# MotorCtrl.net
KiCad netlist of a schematic drawn in Altium Designer
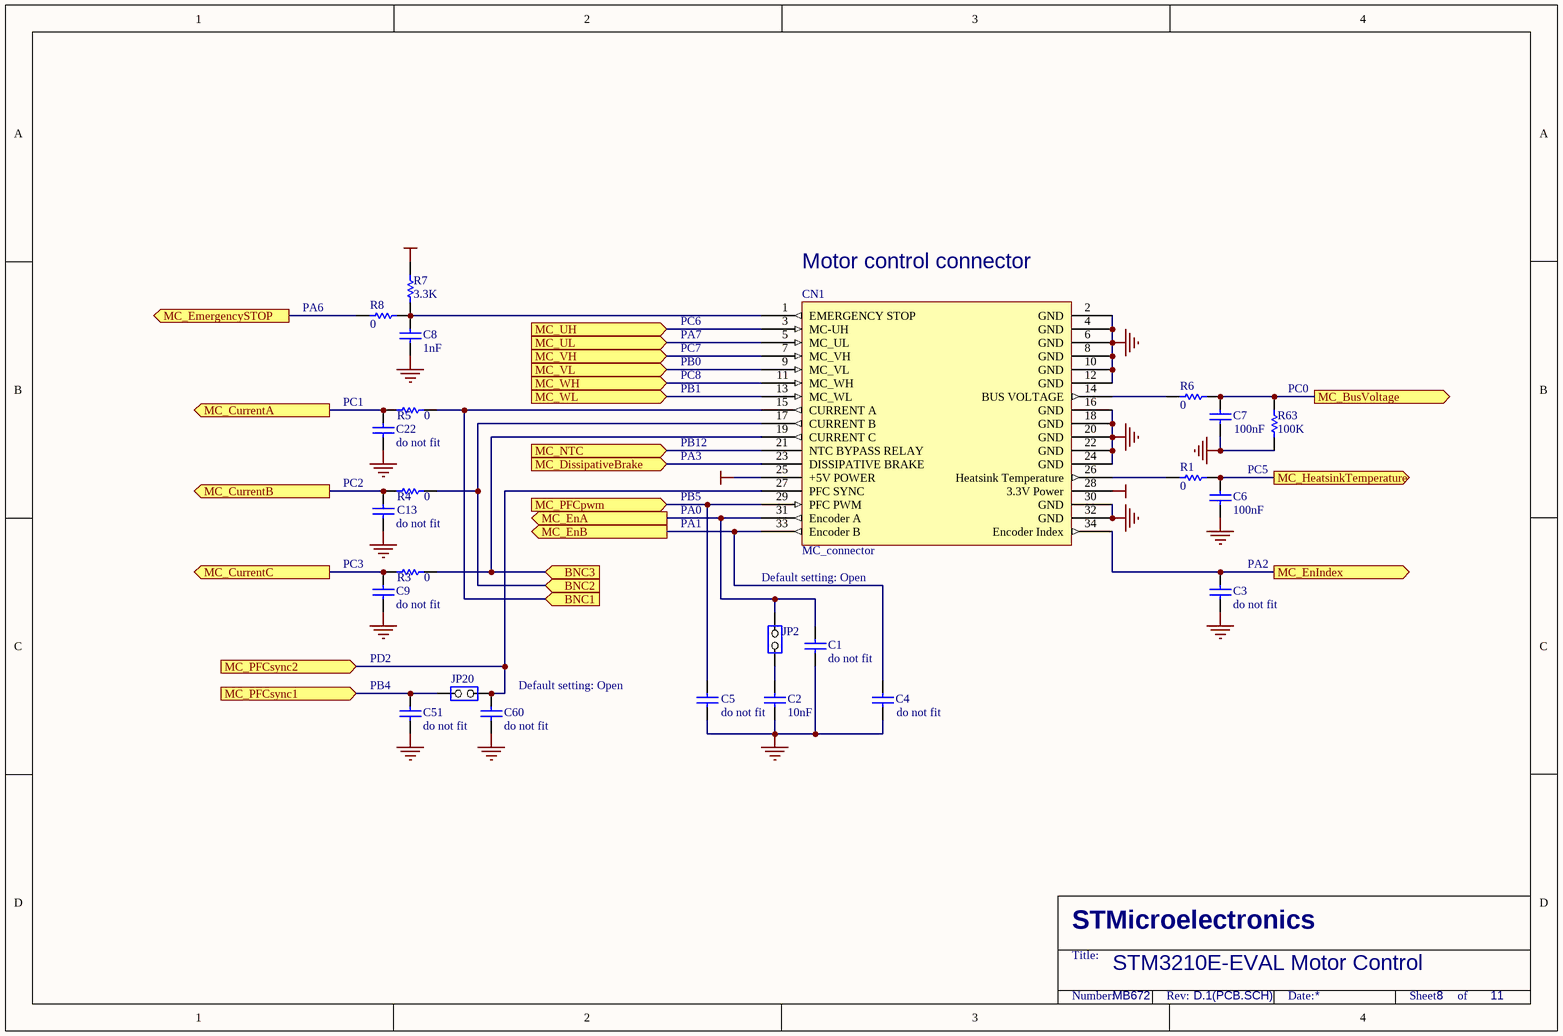
[diagram p0: MotorCtrl.SchDoc]

(export (version "E")
  (design (tool "Eeschema 10.0.6"))
  (components
    (comp (ref "C1")
      (value "do not fit")
      (description "Capacitor")
      (fields (field (name "PUBLISHER") "Altium Limited"))
      (libsource (lib "Miscellaneous Devices") (part "cap"))
    )
    (comp (ref "C2")
      (value "10nF")
      (description "Capacitor")
      (fields (field (name "PUBLISHER") "Altium Limited"))
      (libsource (lib "Miscellaneous Devices") (part "cap"))
    )
    (comp (ref "C3")
      (value "do not fit")
      (description "Capacitor")
      (fields (field (name "PUBLISHER") "Altium Limited"))
      (libsource (lib "Miscellaneous Devices") (part "cap"))
    )
    (comp (ref "C4")
      (value "do not fit")
      (description "Capacitor")
      (fields (field (name "PUBLISHER") "Altium Limited"))
      (libsource (lib "Miscellaneous Devices") (part "cap"))
    )
    (comp (ref "C5")
      (value "do not fit")
      (description "Capacitor")
      (fields (field (name "PUBLISHER") "Altium Limited"))
      (libsource (lib "Miscellaneous Devices") (part "cap"))
    )
    (comp (ref "C6")
      (value "100nF")
      (description "Capacitor")
      (fields (field (name "PUBLISHER") "Altium Limited"))
      (libsource (lib "Miscellaneous Devices") (part "cap"))
    )
    (comp (ref "C7")
      (value "100nF")
      (description "Capacitor")
      (fields (field (name "PUBLISHER") "Altium Limited"))
      (libsource (lib "Miscellaneous Devices") (part "cap"))
    )
    (comp (ref "C8")
      (value "1nF")
      (description "Capacitor")
      (fields (field (name "PUBLISHER") "Altium Limited"))
      (libsource (lib "Miscellaneous Devices") (part "CAP"))
    )
    (comp (ref "C9")
      (value "do not fit")
      (description "Capacitor")
      (fields (field (name "PUBLISHER") "Altium Limited"))
      (libsource (lib "Miscellaneous Devices") (part "cap"))
    )
    (comp (ref "C13")
      (value "do not fit")
      (description "Capacitor")
      (fields (field (name "PUBLISHER") "Altium Limited"))
      (libsource (lib "Miscellaneous Devices") (part "cap"))
    )
    (comp (ref "C22")
      (value "do not fit")
      (description "Capacitor")
      (fields (field (name "PUBLISHER") "Altium Limited"))
      (libsource (lib "Miscellaneous Devices") (part "cap"))
    )
    (comp (ref "C51")
      (value "do not fit")
      (description "Capacitor")
      (fields (field (name "PUBLISHER") "Altium Limited"))
      (libsource (lib "Miscellaneous Devices") (part "cap"))
    )
    (comp (ref "C60")
      (value "do not fit")
      (description "Capacitor")
      (fields (field (name "PUBLISHER") "Altium Limited"))
      (libsource (lib "Miscellaneous Devices") (part "cap"))
    )
    (comp (ref "CN1")
      (value "MC_connector")
      (footprint "IDC34S")
      (libsource (lib "MB525") (part "MC_connector"))
    )
    (comp (ref "JP2") (value "~") (footprint "SIP2") (libsource (lib "*") (part "JP2")))
    (comp (ref "JP20") (value "~") (footprint "SIP2") (libsource (lib "*") (part "JP2")))
    (comp (ref "R1")
      (value "0")
      (footprint "0603")
      (description "Resistor")
      (fields (field (name "PUBLISHER") "Altium Limited"))
      (libsource (lib "Miscellaneous Devices") (part "Res1"))
    )
    (comp (ref "R3")
      (value "0")
      (footprint "0603")
      (description "Resistor")
      (fields (field (name "PUBLISHER") "Altium Limited"))
      (libsource (lib "Miscellaneous Devices") (part "Res1"))
    )
    (comp (ref "R4")
      (value "0")
      (footprint "0603")
      (description "Resistor")
      (fields (field (name "PUBLISHER") "Altium Limited"))
      (libsource (lib "Miscellaneous Devices") (part "Res1"))
    )
    (comp (ref "R5")
      (value "0")
      (footprint "0603")
      (description "Resistor")
      (fields (field (name "PUBLISHER") "Altium Limited"))
      (libsource (lib "Miscellaneous Devices") (part "Res1"))
    )
    (comp (ref "R6")
      (value "0")
      (footprint "0603")
      (description "Resistor")
      (fields (field (name "PUBLISHER") "Altium Limited"))
      (libsource (lib "Miscellaneous Devices") (part "Res1"))
    )
    (comp (ref "R7")
      (value "3.3K")
      (description "Resistor")
      (fields (field (name "PUBLISHER") "Altium Limited"))
      (libsource (lib "Miscellaneous Devices") (part "Res1"))
    )
    (comp (ref "R8")
      (value "0")
      (description "Resistor")
      (fields (field (name "PUBLISHER") "Altium Limited"))
      (libsource (lib "Miscellaneous Devices") (part "Res1"))
    )
    (comp (ref "R63")
      (value "100K")
      (footprint "0603")
      (description "Resistor")
      (fields (field (name "PUBLISHER") "Altium Limited"))
      (libsource (lib "Miscellaneous Devices") (part "Res1"))
    )
  )
  (nets
    (net (code "1") (name "+3V3") (class "Default")
      (node (ref "CN1") (pin "28") (pinfunction "3.3V_Power_28") (pintype "power_in"))
      (node (ref "R7") (pin "2") (pinfunction "2_2") (pintype "passive"))
    )
    (net (code "2") (name "+5V") (class "Default")
      (node (ref "CN1") (pin "25") (pinfunction "+5V_POWER_25") (pintype "power_in"))
    )
    (net (code "3") (name "/BNC1") (class "Default")
      (node (ref "CN1") (pin "15") (pinfunction "CURRENT_A_15") (pintype "output"))
      (node (ref "R5") (pin "2") (pinfunction "2_2") (pintype "passive"))
    )
    (net (code "4") (name "/BNC2") (class "Default")
      (node (ref "CN1") (pin "17") (pinfunction "CURRENT_B_17") (pintype "output"))
      (node (ref "R4") (pin "2") (pinfunction "2_2") (pintype "passive"))
    )
    (net (code "5") (name "/BNC3") (class "Default")
      (node (ref "CN1") (pin "19") (pinfunction "CURRENT_C_19") (pintype "output"))
      (node (ref "R3") (pin "2") (pinfunction "2_2") (pintype "passive"))
    )
    (net (code "6") (name "/MC_BusVoltage") (class "Default")
      (node (ref "C7") (pin "2") (pinfunction "2_2") (pintype "passive"))
      (node (ref "R6") (pin "2") (pinfunction "2_2") (pintype "passive"))
      (node (ref "R63") (pin "2") (pinfunction "2_2") (pintype "passive"))
    )
    (net (code "7") (name "/MC_CurrentA") (class "Default")
      (node (ref "C22") (pin "2") (pinfunction "2_2") (pintype "passive"))
      (node (ref "R5") (pin "1") (pinfunction "1_1") (pintype "passive"))
    )
    (net (code "8") (name "/MC_CurrentB") (class "Default")
      (node (ref "C13") (pin "2") (pinfunction "2_2") (pintype "passive"))
      (node (ref "R4") (pin "1") (pinfunction "1_1") (pintype "passive"))
    )
    (net (code "9") (name "/MC_CurrentC") (class "Default")
      (node (ref "C9") (pin "2") (pinfunction "2_2") (pintype "passive"))
      (node (ref "R3") (pin "1") (pinfunction "1_1") (pintype "passive"))
    )
    (net (code "10") (name "/MC_DissipativeBrake") (class "Default")
      (node (ref "CN1") (pin "23") (pinfunction "DISSIPATIVE_BRAKE_23") (pintype "passive"))
    )
    (net (code "11") (name "/MC_EmergencySTOP") (class "Default")
      (node (ref "R8") (pin "2") (pinfunction "2_2") (pintype "passive"))
    )
    (net (code "12") (name "/MC_EnA") (class "Default")
      (node (ref "C1") (pin "2") (pinfunction "2_2") (pintype "passive"))
      (node (ref "CN1") (pin "31") (pinfunction "Encoder_A_31") (pintype "output"))
      (node (ref "JP2") (pin "1") (pinfunction "COMMON_1") (pintype "passive"))
    )
    (net (code "13") (name "/MC_EnB") (class "Default")
      (node (ref "C4") (pin "2") (pinfunction "2_2") (pintype "passive"))
      (node (ref "CN1") (pin "33") (pinfunction "Encoder_B_33") (pintype "output"))
    )
    (net (code "14") (name "/MC_EnIndex") (class "Default")
      (node (ref "C3") (pin "2") (pinfunction "2_2") (pintype "passive"))
      (node (ref "CN1") (pin "34") (pinfunction "Encoder_Index_34") (pintype "output"))
    )
    (net (code "15") (name "/MC_HeatsinkTemperature") (class "Default")
      (node (ref "C6") (pin "2") (pinfunction "2_2") (pintype "passive"))
      (node (ref "R1") (pin "2") (pinfunction "2_2") (pintype "passive"))
    )
    (net (code "16") (name "/MC_NTC") (class "Default")
      (node (ref "CN1") (pin "21") (pinfunction "NTC_BYPASS_RELAY_21") (pintype "passive"))
    )
    (net (code "17") (name "/MC_PFCpwm") (class "Default")
      (node (ref "C5") (pin "2") (pinfunction "2_2") (pintype "passive"))
      (node (ref "CN1") (pin "29") (pinfunction "PFC_PWM_29") (pintype "input"))
    )
    (net (code "18") (name "/MC_PFCsync1") (class "Default")
      (node (ref "C51") (pin "2") (pinfunction "2_2") (pintype "passive"))
      (node (ref "JP20") (pin "2") (pinfunction "NO_2") (pintype "passive"))
    )
    (net (code "19") (name "/MC_PFCsync2") (class "Default")
      (node (ref "C60") (pin "2") (pinfunction "2_2") (pintype "passive"))
      (node (ref "CN1") (pin "27") (pinfunction "PFC_SYNC_27") (pintype "passive"))
      (node (ref "JP20") (pin "1") (pinfunction "COMMON_1") (pintype "passive"))
    )
    (net (code "20") (name "/MC_UH") (class "Default")
      (node (ref "CN1") (pin "3") (pinfunction "MC-UH_3") (pintype "input"))
    )
    (net (code "21") (name "/MC_UL") (class "Default")
      (node (ref "CN1") (pin "5") (pinfunction "MC_UL_5") (pintype "input"))
    )
    (net (code "22") (name "/MC_VH") (class "Default")
      (node (ref "CN1") (pin "7") (pinfunction "MC_VH_7") (pintype "input"))
    )
    (net (code "23") (name "/MC_VL") (class "Default")
      (node (ref "CN1") (pin "9") (pinfunction "MC_VL_9") (pintype "input"))
    )
    (net (code "24") (name "/MC_WH") (class "Default")
      (node (ref "CN1") (pin "11") (pinfunction "MC_WH_11") (pintype "input"))
    )
    (net (code "25") (name "/MC_WL") (class "Default")
      (node (ref "CN1") (pin "13") (pinfunction "MC_WL_13") (pintype "input"))
    )
    (net (code "26") (name "GND") (class "Default")
      (node (ref "C1") (pin "1") (pinfunction "1_1") (pintype "passive"))
      (node (ref "C13") (pin "1") (pinfunction "1_1") (pintype "passive"))
      (node (ref "C2") (pin "1") (pinfunction "1_1") (pintype "passive"))
      (node (ref "C22") (pin "1") (pinfunction "1_1") (pintype "passive"))
      (node (ref "C3") (pin "1") (pinfunction "1_1") (pintype "passive"))
      (node (ref "C4") (pin "1") (pinfunction "1_1") (pintype "passive"))
      (node (ref "C5") (pin "1") (pinfunction "1_1") (pintype "passive"))
      (node (ref "C51") (pin "1") (pinfunction "1_1") (pintype "passive"))
      (node (ref "C6") (pin "1") (pinfunction "1_1") (pintype "passive"))
      (node (ref "C60") (pin "1") (pinfunction "1_1") (pintype "passive"))
      (node (ref "C7") (pin "1") (pinfunction "1_1") (pintype "passive"))
      (node (ref "C8") (pin "1") (pinfunction "1_1") (pintype "passive"))
      (node (ref "C9") (pin "1") (pinfunction "1_1") (pintype "passive"))
      (node (ref "CN1") (pin "10") (pinfunction "GND_10") (pintype "power_in"))
      (node (ref "CN1") (pin "12") (pinfunction "GND_12") (pintype "power_in"))
      (node (ref "CN1") (pin "16") (pinfunction "GND_16") (pintype "power_in"))
      (node (ref "CN1") (pin "18") (pinfunction "GND_18") (pintype "power_in"))
      (node (ref "CN1") (pin "2") (pinfunction "GND_2") (pintype "power_in"))
      (node (ref "CN1") (pin "20") (pinfunction "GND_20") (pintype "power_in"))
      (node (ref "CN1") (pin "22") (pinfunction "GND_22") (pintype "power_in"))
      (node (ref "CN1") (pin "24") (pinfunction "GND_24") (pintype "power_in"))
      (node (ref "CN1") (pin "30") (pinfunction "GND_30") (pintype "power_in"))
      (node (ref "CN1") (pin "32") (pinfunction "GND_32") (pintype "power_in"))
      (node (ref "CN1") (pin "4") (pinfunction "GND_4") (pintype "power_in"))
      (node (ref "CN1") (pin "6") (pinfunction "GND_6") (pintype "power_in"))
      (node (ref "CN1") (pin "8") (pinfunction "GND_8") (pintype "power_in"))
      (node (ref "R63") (pin "1") (pinfunction "1_1") (pintype "passive"))
    )
    (net (code "27") (name "Net-(CN1-BUS_VOLTAGE)") (class "Default")
      (node (ref "CN1") (pin "14") (pinfunction "BUS_VOLTAGE_14") (pintype "output"))
      (node (ref "R6") (pin "1") (pinfunction "1_1") (pintype "passive"))
    )
    (net (code "28") (name "Net-(CN1-EMERGENCY_STOP)") (class "Default")
      (node (ref "C8") (pin "2") (pinfunction "2_2") (pintype "passive"))
      (node (ref "CN1") (pin "1") (pinfunction "EMERGENCY_STOP_1") (pintype "output"))
      (node (ref "R7") (pin "1") (pinfunction "1_1") (pintype "passive"))
      (node (ref "R8") (pin "1") (pinfunction "1_1") (pintype "passive"))
    )
    (net (code "29") (name "Net-(CN1-Heatsink_Temperature)") (class "Default")
      (node (ref "CN1") (pin "26") (pinfunction "Heatsink_Temperature_26") (pintype "output"))
      (node (ref "R1") (pin "1") (pinfunction "1_1") (pintype "passive"))
    )
    (net (code "30") (name "Net-(JP2-NO)") (class "Default")
      (node (ref "C2") (pin "2") (pinfunction "2_2") (pintype "passive"))
      (node (ref "JP2") (pin "2") (pinfunction "NO_2") (pintype "passive"))
    )
  )
)
